# ADC.net
KiCad netlist of a schematic drawn in Altium Designer
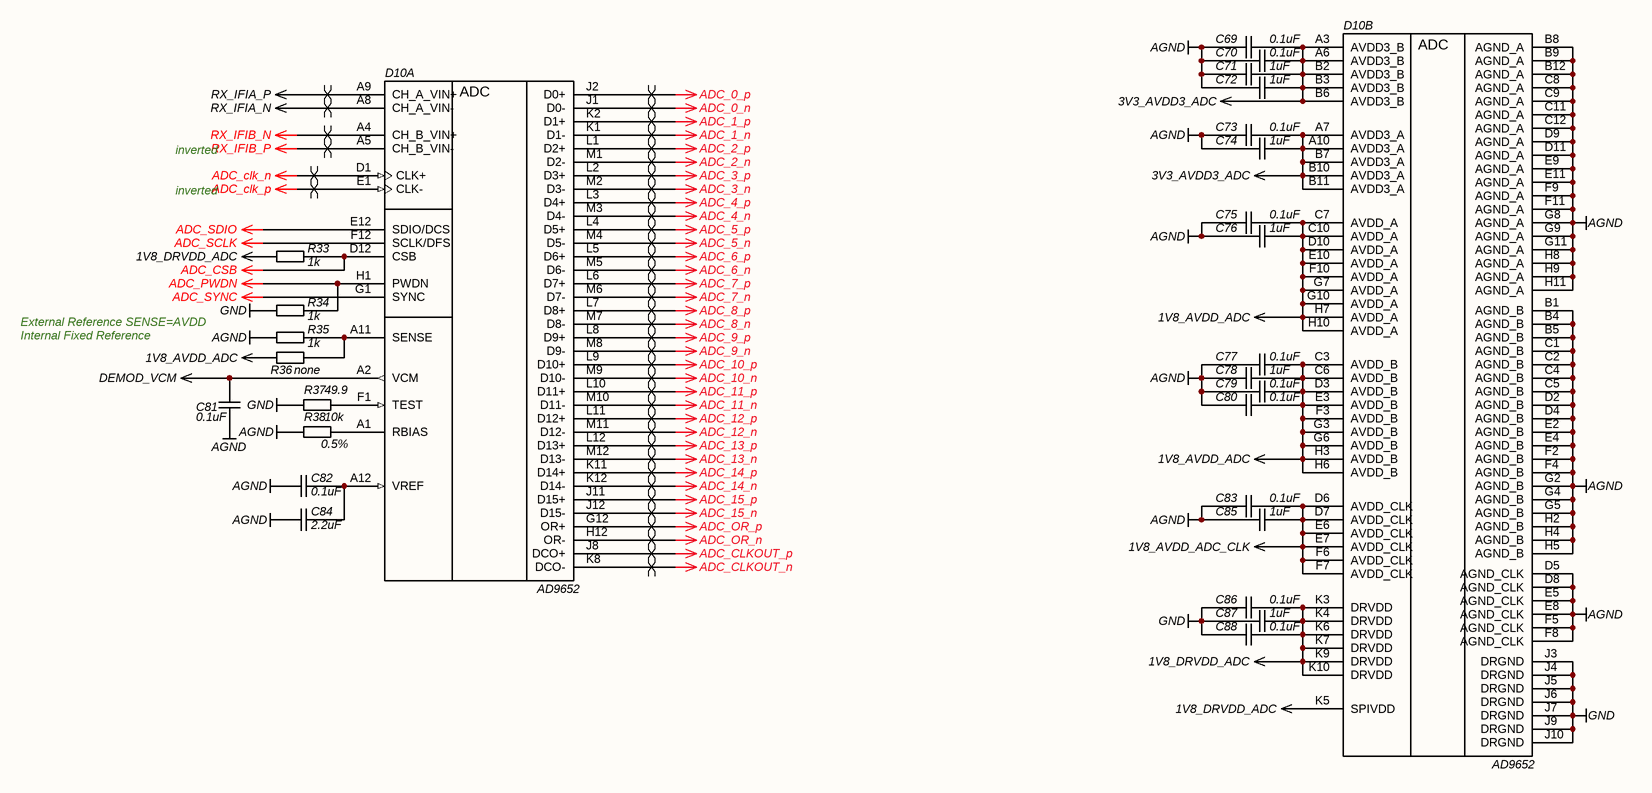
[diagram p0: ADC.SchDoc]

(export (version "E")
  (design (tool "Eeschema 10.0.6"))
  (components
    (comp (ref "C69")
      (value "0.1uF")
      (footprint "C0402")
      (description "SMD Capacitor")
      (fields (field (name "MANUFACTURER") "Murata") (field (name "TOLERANCE") "10%"))
      (libsource (lib "Kintex_SDR") (part "CAP"))
    )
    (comp (ref "C70")
      (value "0.1uF")
      (footprint "C0402")
      (description "SMD Capacitor")
      (fields (field (name "MANUFACTURER") "Murata") (field (name "TOLERANCE") "10%"))
      (libsource (lib "Kintex_SDR") (part "CAP"))
    )
    (comp (ref "C71")
      (value "1uF")
      (footprint "C0402")
      (description "SMD Capacitor")
      (fields (field (name "MANUFACTURER") "Murata") (field (name "TOLERANCE") "10%"))
      (libsource (lib "Kintex_SDR") (part "CAP"))
    )
    (comp (ref "C72")
      (value "1uF")
      (footprint "C0402")
      (description "SMD Capacitor")
      (fields (field (name "MANUFACTURER") "Murata") (field (name "TOLERANCE") "10%"))
      (libsource (lib "Kintex_SDR") (part "CAP"))
    )
    (comp (ref "C73")
      (value "0.1uF")
      (footprint "C0402")
      (description "SMD Capacitor")
      (fields (field (name "MANUFACTURER") "Murata") (field (name "TOLERANCE") "10%"))
      (libsource (lib "Kintex_SDR") (part "CAP"))
    )
    (comp (ref "C74")
      (value "1uF")
      (footprint "C0402")
      (description "SMD Capacitor")
      (fields (field (name "MANUFACTURER") "Murata") (field (name "TOLERANCE") "10%"))
      (libsource (lib "Kintex_SDR") (part "CAP"))
    )
    (comp (ref "C75")
      (value "0.1uF")
      (footprint "C0402")
      (description "SMD Capacitor")
      (fields (field (name "MANUFACTURER") "Murata") (field (name "TOLERANCE") "10%"))
      (libsource (lib "Kintex_SDR") (part "CAP"))
    )
    (comp (ref "C76")
      (value "1uF")
      (footprint "C0402")
      (description "SMD Capacitor")
      (fields (field (name "MANUFACTURER") "Murata") (field (name "TOLERANCE") "10%"))
      (libsource (lib "Kintex_SDR") (part "CAP"))
    )
    (comp (ref "C77")
      (value "0.1uF")
      (footprint "C0402")
      (description "SMD Capacitor")
      (fields (field (name "MANUFACTURER") "Murata") (field (name "TOLERANCE") "10%"))
      (libsource (lib "Kintex_SDR") (part "CAP"))
    )
    (comp (ref "C78")
      (value "1uF")
      (footprint "C0402")
      (description "SMD Capacitor")
      (fields (field (name "MANUFACTURER") "Murata") (field (name "TOLERANCE") "10%"))
      (libsource (lib "Kintex_SDR") (part "CAP"))
    )
    (comp (ref "C79")
      (value "0.1uF")
      (footprint "C0402")
      (description "SMD Capacitor")
      (fields (field (name "MANUFACTURER") "Murata") (field (name "TOLERANCE") "10%"))
      (libsource (lib "Kintex_SDR") (part "CAP"))
    )
    (comp (ref "C80")
      (value "0.1uF")
      (footprint "C0402")
      (description "SMD Capacitor")
      (fields (field (name "MANUFACTURER") "Murata") (field (name "TOLERANCE") "10%"))
      (libsource (lib "Kintex_SDR") (part "CAP"))
    )
    (comp (ref "C81")
      (value "0.1uF")
      (footprint "C0402")
      (description "SMD Capacitor")
      (fields (field (name "MANUFACTURER") "Murata") (field (name "TOLERANCE") "10%"))
      (libsource (lib "Kintex_SDR") (part "CAP"))
    )
    (comp (ref "C82")
      (value "0.1uF")
      (footprint "C0402")
      (description "SMD Capacitor")
      (fields (field (name "MANUFACTURER") "Murata") (field (name "TOLERANCE") "10%"))
      (libsource (lib "Kintex_SDR") (part "CAP"))
    )
    (comp (ref "C83")
      (value "0.1uF")
      (footprint "C0402")
      (description "SMD Capacitor")
      (fields (field (name "MANUFACTURER") "Murata") (field (name "TOLERANCE") "10%"))
      (libsource (lib "Kintex_SDR") (part "CAP"))
    )
    (comp (ref "C84")
      (value "2.2uF")
      (footprint "C0603")
      (description "SMD Capacitor")
      (fields (field (name "MANUFACTURER") "Murata") (field (name "TOLERANCE") "10%"))
      (libsource (lib "Kintex_SDR") (part "CAP"))
    )
    (comp (ref "C85")
      (value "1uF")
      (footprint "C0402")
      (description "SMD Capacitor")
      (fields (field (name "MANUFACTURER") "Murata") (field (name "TOLERANCE") "10%"))
      (libsource (lib "Kintex_SDR") (part "CAP"))
    )
    (comp (ref "C86")
      (value "0.1uF")
      (footprint "C0402")
      (description "SMD Capacitor")
      (fields (field (name "MANUFACTURER") "Murata") (field (name "TOLERANCE") "10%"))
      (libsource (lib "Kintex_SDR") (part "CAP"))
    )
    (comp (ref "C87")
      (value "1uF")
      (footprint "C0402")
      (description "SMD Capacitor")
      (fields (field (name "MANUFACTURER") "Murata") (field (name "TOLERANCE") "10%"))
      (libsource (lib "Kintex_SDR") (part "CAP"))
    )
    (comp (ref "C88")
      (value "0.1uF")
      (footprint "C0402")
      (description "SMD Capacitor")
      (fields (field (name "MANUFACTURER") "Murata") (field (name "TOLERANCE") "10%"))
      (libsource (lib "Kintex_SDR") (part "CAP"))
    )
    (comp (ref "D10")
      (value "AD9652")
      (footprint "DBLib:BGA144x12")
      (description "Dual, 16-bit analog-to-digital converter (ADC)\r\nwith sampling speeds of up to 310 MSPS")
      (fields (field (name "MANUFACTURER") "Analog Devices"))
      (libsource (lib "DBLib") (part "AD9652"))
    )
    (comp (ref "R33")
      (value "1k")
      (footprint "R0402")
      (description "SMD Resistor")
      (fields (field (name "POWER") "0.062 Wt") (field (name "TOLERANCE") "5%"))
      (libsource (lib "") (part "RES_2"))
    )
    (comp (ref "R34")
      (value "1k")
      (footprint "R0402")
      (description "SMD Resistor")
      (fields (field (name "POWER") "0.062 Wt") (field (name "TOLERANCE") "5%"))
      (libsource (lib "") (part "RES_2"))
    )
    (comp (ref "R35")
      (value "1k")
      (footprint "R0402")
      (description "SMD Resistor")
      (fields (field (name "POWER") "0.062 Wt") (field (name "TOLERANCE") "5%"))
      (libsource (lib "") (part "RES_2"))
    )
    (comp (ref "R36")
      (value "none")
      (footprint "R0402")
      (description "SMD Resistor")
      (fields
        (field (name "POWER") "0.062 Wt")
        (field (name "MANUFACTURER") "Panasonic Electronic Components")
      )
      (libsource (lib "") (part "RES_2"))
    )
    (comp (ref "R37")
      (value "49.9")
      (footprint "R0402")
      (description "SMD Resistor")
      (fields (field (name "POWER") "0.063 Wt") (field (name "TOLERANCE") "0.5%"))
      (libsource (lib "Kintex_SDR") (part "RES"))
    )
    (comp (ref "R38")
      (value "10k")
      (footprint "R0402")
      (description "SMD Resistor")
      (fields
        (field (name "POWER") "0.063 Wt")
        (field (name "TOLERANCE") "0.5%")
        (field (name "MANUFACTURER") "Panasonic Electronic Components")
      )
      (libsource (lib "") (part "RES_1"))
    )
  )
  (nets
    (net (code "1") (name "1V8_AVDD_ADC") (class "Default")
      (node (ref "C75") (pin "2") (pinfunction "2_2") (pintype "passive"))
      (node (ref "C76") (pin "2") (pinfunction "2_2") (pintype "passive"))
      (node (ref "C77") (pin "2") (pinfunction "2_2") (pintype "passive"))
      (node (ref "C78") (pin "2") (pinfunction "2_2") (pintype "passive"))
      (node (ref "C79") (pin "2") (pinfunction "2_2") (pintype "passive"))
      (node (ref "C80") (pin "2") (pinfunction "2_2") (pintype "passive"))
      (node (ref "D10") (pin "C10") (pinfunction "AVDD_A_C10") (pintype "passive"))
      (node (ref "D10") (pin "C3") (pinfunction "AVDD_B_C3") (pintype "passive"))
      (node (ref "D10") (pin "C6") (pinfunction "AVDD_B_C6") (pintype "passive"))
      (node (ref "D10") (pin "C7") (pinfunction "AVDD_A_C7") (pintype "passive"))
      (node (ref "D10") (pin "D10") (pinfunction "AVDD_A_D10") (pintype "passive"))
      (node (ref "D10") (pin "D3") (pinfunction "AVDD_B_D3") (pintype "passive"))
      (node (ref "D10") (pin "E10") (pinfunction "AVDD_A_E10") (pintype "passive"))
      (node (ref "D10") (pin "E3") (pinfunction "AVDD_B_E3") (pintype "passive"))
      (node (ref "D10") (pin "F10") (pinfunction "AVDD_A_F10") (pintype "passive"))
      (node (ref "D10") (pin "F3") (pinfunction "AVDD_B_F3") (pintype "passive"))
      (node (ref "D10") (pin "G10") (pinfunction "AVDD_A_G10") (pintype "passive"))
      (node (ref "D10") (pin "G3") (pinfunction "AVDD_B_G3") (pintype "passive"))
      (node (ref "D10") (pin "G6") (pinfunction "AVDD_B_G6") (pintype "passive"))
      (node (ref "D10") (pin "G7") (pinfunction "AVDD_A_G7") (pintype "passive"))
      (node (ref "D10") (pin "H10") (pinfunction "AVDD_A_H10") (pintype "passive"))
      (node (ref "D10") (pin "H3") (pinfunction "AVDD_B_H3") (pintype "passive"))
      (node (ref "D10") (pin "H6") (pinfunction "AVDD_B_H6") (pintype "passive"))
      (node (ref "D10") (pin "H7") (pinfunction "AVDD_A_H7") (pintype "passive"))
      (node (ref "R36") (pin "2") (pinfunction "2_2") (pintype "passive"))
    )
    (net (code "2") (name "1V8_AVDD_ADC_CLK") (class "Default")
      (node (ref "C83") (pin "2") (pinfunction "2_2") (pintype "passive"))
      (node (ref "C85") (pin "2") (pinfunction "2_2") (pintype "passive"))
      (node (ref "D10") (pin "D6") (pinfunction "AVDD_CLK_D6") (pintype "passive"))
      (node (ref "D10") (pin "D7") (pinfunction "AVDD_CLK_D7") (pintype "passive"))
      (node (ref "D10") (pin "E6") (pinfunction "AVDD_CLK_E6") (pintype "passive"))
      (node (ref "D10") (pin "E7") (pinfunction "AVDD_CLK_E7") (pintype "passive"))
      (node (ref "D10") (pin "F6") (pinfunction "AVDD_CLK_F6") (pintype "passive"))
      (node (ref "D10") (pin "F7") (pinfunction "AVDD_CLK_F7") (pintype "passive"))
    )
    (net (code "3") (name "1V8_DRVDD_ADC") (class "Default")
      (node (ref "C86") (pin "2") (pinfunction "2_2") (pintype "passive"))
      (node (ref "C87") (pin "2") (pinfunction "2_2") (pintype "passive"))
      (node (ref "C88") (pin "2") (pinfunction "2_2") (pintype "passive"))
      (node (ref "D10") (pin "K10") (pinfunction "DRVDD_K10") (pintype "passive"))
      (node (ref "D10") (pin "K3") (pinfunction "DRVDD_K3") (pintype "passive"))
      (node (ref "D10") (pin "K4") (pinfunction "DRVDD_K4") (pintype "passive"))
      (node (ref "D10") (pin "K5") (pinfunction "SPIVDD_K5") (pintype "passive"))
      (node (ref "D10") (pin "K6") (pinfunction "DRVDD_K6") (pintype "passive"))
      (node (ref "D10") (pin "K7") (pinfunction "DRVDD_K7") (pintype "passive"))
      (node (ref "D10") (pin "K9") (pinfunction "DRVDD_K9") (pintype "passive"))
      (node (ref "R33") (pin "2") (pinfunction "2_2") (pintype "passive"))
    )
    (net (code "4") (name "3V3_AVDD3_ADC") (class "Default")
      (node (ref "C69") (pin "2") (pinfunction "2_2") (pintype "passive"))
      (node (ref "C70") (pin "2") (pinfunction "2_2") (pintype "passive"))
      (node (ref "C71") (pin "2") (pinfunction "2_2") (pintype "passive"))
      (node (ref "C72") (pin "2") (pinfunction "2_2") (pintype "passive"))
      (node (ref "C73") (pin "2") (pinfunction "2_2") (pintype "passive"))
      (node (ref "C74") (pin "2") (pinfunction "2_2") (pintype "passive"))
      (node (ref "D10") (pin "A10") (pinfunction "AVDD3_A_A10") (pintype "passive"))
      (node (ref "D10") (pin "A3") (pinfunction "AVDD3_B_A3") (pintype "passive"))
      (node (ref "D10") (pin "A6") (pinfunction "AVDD3_B_A6") (pintype "passive"))
      (node (ref "D10") (pin "A7") (pinfunction "AVDD3_A_A7") (pintype "passive"))
      (node (ref "D10") (pin "B10") (pinfunction "AVDD3_A_B10") (pintype "passive"))
      (node (ref "D10") (pin "B11") (pinfunction "AVDD3_A_B11") (pintype "passive"))
      (node (ref "D10") (pin "B2") (pinfunction "AVDD3_B_B2") (pintype "passive"))
      (node (ref "D10") (pin "B3") (pinfunction "AVDD3_B_B3") (pintype "passive"))
      (node (ref "D10") (pin "B6") (pinfunction "AVDD3_B_B6") (pintype "passive"))
      (node (ref "D10") (pin "B7") (pinfunction "AVDD3_A_B7") (pintype "passive"))
    )
    (net (code "5") (name "ADC_0_n") (class "Default")
      (node (ref "D10") (pin "J1") (pinfunction "D0-_J1") (pintype "passive"))
    )
    (net (code "6") (name "ADC_0_p") (class "Default")
      (node (ref "D10") (pin "J2") (pinfunction "D0+_J2") (pintype "passive"))
    )
    (net (code "7") (name "ADC_1_n") (class "Default")
      (node (ref "D10") (pin "K1") (pinfunction "D1-_K1") (pintype "passive"))
    )
    (net (code "8") (name "ADC_1_p") (class "Default")
      (node (ref "D10") (pin "K2") (pinfunction "D1+_K2") (pintype "passive"))
    )
    (net (code "9") (name "ADC_2_n") (class "Default")
      (node (ref "D10") (pin "M1") (pinfunction "D2-_M1") (pintype "passive"))
    )
    (net (code "10") (name "ADC_2_p") (class "Default")
      (node (ref "D10") (pin "L1") (pinfunction "D2+_L1") (pintype "passive"))
    )
    (net (code "11") (name "ADC_3_n") (class "Default")
      (node (ref "D10") (pin "M2") (pinfunction "D3-_M2") (pintype "passive"))
    )
    (net (code "12") (name "ADC_3_p") (class "Default")
      (node (ref "D10") (pin "L2") (pinfunction "D3+_L2") (pintype "passive"))
    )
    (net (code "13") (name "ADC_4_n") (class "Default")
      (node (ref "D10") (pin "M3") (pinfunction "D4-_M3") (pintype "passive"))
    )
    (net (code "14") (name "ADC_4_p") (class "Default")
      (node (ref "D10") (pin "L3") (pinfunction "D4+_L3") (pintype "passive"))
    )
    (net (code "15") (name "ADC_5_n") (class "Default")
      (node (ref "D10") (pin "M4") (pinfunction "D5-_M4") (pintype "passive"))
    )
    (net (code "16") (name "ADC_5_p") (class "Default")
      (node (ref "D10") (pin "L4") (pinfunction "D5+_L4") (pintype "passive"))
    )
    (net (code "17") (name "ADC_6_n") (class "Default")
      (node (ref "D10") (pin "M5") (pinfunction "D6-_M5") (pintype "passive"))
    )
    (net (code "18") (name "ADC_6_p") (class "Default")
      (node (ref "D10") (pin "L5") (pinfunction "D6+_L5") (pintype "passive"))
    )
    (net (code "19") (name "ADC_7_n") (class "Default")
      (node (ref "D10") (pin "M6") (pinfunction "D7-_M6") (pintype "passive"))
    )
    (net (code "20") (name "ADC_7_p") (class "Default")
      (node (ref "D10") (pin "L6") (pinfunction "D7+_L6") (pintype "passive"))
    )
    (net (code "21") (name "ADC_8_n") (class "Default")
      (node (ref "D10") (pin "M7") (pinfunction "D8-_M7") (pintype "passive"))
    )
    (net (code "22") (name "ADC_8_p") (class "Default")
      (node (ref "D10") (pin "L7") (pinfunction "D8+_L7") (pintype "passive"))
    )
    (net (code "23") (name "ADC_9_n") (class "Default")
      (node (ref "D10") (pin "M8") (pinfunction "D9-_M8") (pintype "passive"))
    )
    (net (code "24") (name "ADC_9_p") (class "Default")
      (node (ref "D10") (pin "L8") (pinfunction "D9+_L8") (pintype "passive"))
    )
    (net (code "25") (name "ADC_10_n") (class "Default")
      (node (ref "D10") (pin "M9") (pinfunction "D10-_M9") (pintype "passive"))
    )
    (net (code "26") (name "ADC_10_p") (class "Default")
      (node (ref "D10") (pin "L9") (pinfunction "D10+_L9") (pintype "passive"))
    )
    (net (code "27") (name "ADC_11_n") (class "Default")
      (node (ref "D10") (pin "M10") (pinfunction "D11-_M10") (pintype "passive"))
    )
    (net (code "28") (name "ADC_11_p") (class "Default")
      (node (ref "D10") (pin "L10") (pinfunction "D11+_L10") (pintype "passive"))
    )
    (net (code "29") (name "ADC_12_n") (class "Default")
      (node (ref "D10") (pin "M11") (pinfunction "D12-_M11") (pintype "passive"))
    )
    (net (code "30") (name "ADC_12_p") (class "Default")
      (node (ref "D10") (pin "L11") (pinfunction "D12+_L11") (pintype "passive"))
    )
    (net (code "31") (name "ADC_13_n") (class "Default")
      (node (ref "D10") (pin "M12") (pinfunction "D13-_M12") (pintype "passive"))
    )
    (net (code "32") (name "ADC_13_p") (class "Default")
      (node (ref "D10") (pin "L12") (pinfunction "D13+_L12") (pintype "passive"))
    )
    (net (code "33") (name "ADC_14_n") (class "Default")
      (node (ref "D10") (pin "K12") (pinfunction "D14-_K12") (pintype "passive"))
    )
    (net (code "34") (name "ADC_14_p") (class "Default")
      (node (ref "D10") (pin "K11") (pinfunction "D14+_K11") (pintype "passive"))
    )
    (net (code "35") (name "ADC_15_n") (class "Default")
      (node (ref "D10") (pin "J12") (pinfunction "D15-_J12") (pintype "passive"))
    )
    (net (code "36") (name "ADC_15_p") (class "Default")
      (node (ref "D10") (pin "J11") (pinfunction "D15+_J11") (pintype "passive"))
    )
    (net (code "37") (name "ADC_CLKOUT_n") (class "Default")
      (node (ref "D10") (pin "K8") (pinfunction "DCO-_K8") (pintype "passive"))
    )
    (net (code "38") (name "ADC_CLKOUT_p") (class "Default")
      (node (ref "D10") (pin "J8") (pinfunction "DCO+_J8") (pintype "passive"))
    )
    (net (code "39") (name "ADC_CSB") (class "Default")
      (node (ref "D10") (pin "D12") (pinfunction "CSB_D12") (pintype "passive"))
      (node (ref "R33") (pin "1") (pinfunction "1_1") (pintype "passive"))
    )
    (net (code "40") (name "ADC_OR_n") (class "Default")
      (node (ref "D10") (pin "H12") (pinfunction "OR-_H12") (pintype "passive"))
    )
    (net (code "41") (name "ADC_OR_p") (class "Default")
      (node (ref "D10") (pin "G12") (pinfunction "OR+_G12") (pintype "passive"))
    )
    (net (code "42") (name "ADC_PWDN") (class "Default")
      (node (ref "D10") (pin "H1") (pinfunction "PWDN_H1") (pintype "passive"))
      (node (ref "R34") (pin "1") (pinfunction "1_1") (pintype "passive"))
    )
    (net (code "43") (name "ADC_SCLK") (class "Default")
      (node (ref "D10") (pin "F12") (pinfunction "SCLK/DFS_F12") (pintype "passive"))
    )
    (net (code "44") (name "ADC_SDIO") (class "Default")
      (node (ref "D10") (pin "E12") (pinfunction "SDIO/DCS_E12") (pintype "passive"))
    )
    (net (code "45") (name "ADC_SYNC") (class "Default")
      (node (ref "D10") (pin "G1") (pinfunction "SYNC_G1") (pintype "passive"))
    )
    (net (code "46") (name "ADC_clk_n") (class "Default")
      (node (ref "D10") (pin "D1") (pinfunction "CLK+_D1") (pintype "input"))
    )
    (net (code "47") (name "ADC_clk_p") (class "Default")
      (node (ref "D10") (pin "E1") (pinfunction "CLK-_E1") (pintype "input"))
    )
    (net (code "48") (name "AGND") (class "Default")
      (node (ref "C69") (pin "1") (pinfunction "1_1") (pintype "passive"))
      (node (ref "C70") (pin "1") (pinfunction "1_1") (pintype "passive"))
      (node (ref "C71") (pin "1") (pinfunction "1_1") (pintype "passive"))
      (node (ref "C72") (pin "1") (pinfunction "1_1") (pintype "passive"))
      (node (ref "C73") (pin "1") (pinfunction "1_1") (pintype "passive"))
      (node (ref "C74") (pin "1") (pinfunction "1_1") (pintype "passive"))
      (node (ref "C75") (pin "1") (pinfunction "1_1") (pintype "passive"))
      (node (ref "C76") (pin "1") (pinfunction "1_1") (pintype "passive"))
      (node (ref "C77") (pin "1") (pinfunction "1_1") (pintype "passive"))
      (node (ref "C78") (pin "1") (pinfunction "1_1") (pintype "passive"))
      (node (ref "C79") (pin "1") (pinfunction "1_1") (pintype "passive"))
      (node (ref "C80") (pin "1") (pinfunction "1_1") (pintype "passive"))
      (node (ref "C81") (pin "1") (pinfunction "1_1") (pintype "passive"))
      (node (ref "C82") (pin "1") (pinfunction "1_1") (pintype "passive"))
      (node (ref "C83") (pin "1") (pinfunction "1_1") (pintype "passive"))
      (node (ref "C84") (pin "2") (pinfunction "2_2") (pintype "passive"))
      (node (ref "C85") (pin "1") (pinfunction "1_1") (pintype "passive"))
      (node (ref "D10") (pin "B1") (pinfunction "AGND_B_B1") (pintype "passive"))
      (node (ref "D10") (pin "B12") (pinfunction "AGND_A_B12") (pintype "passive"))
      (node (ref "D10") (pin "B4") (pinfunction "AGND_B_B4") (pintype "passive"))
      (node (ref "D10") (pin "B5") (pinfunction "AGND_B_B5") (pintype "passive"))
      (node (ref "D10") (pin "B8") (pinfunction "AGND_A_B8") (pintype "passive"))
      (node (ref "D10") (pin "B9") (pinfunction "AGND_A_B9") (pintype "passive"))
      (node (ref "D10") (pin "C1") (pinfunction "AGND_B_C1") (pintype "passive"))
      (node (ref "D10") (pin "C11") (pinfunction "AGND_A_C11") (pintype "passive"))
      (node (ref "D10") (pin "C12") (pinfunction "AGND_A_C12") (pintype "passive"))
      (node (ref "D10") (pin "C2") (pinfunction "AGND_B_C2") (pintype "passive"))
      (node (ref "D10") (pin "C4") (pinfunction "AGND_B_C4") (pintype "passive"))
      (node (ref "D10") (pin "C5") (pinfunction "AGND_B_C5") (pintype "passive"))
      (node (ref "D10") (pin "C8") (pinfunction "AGND_A_C8") (pintype "passive"))
      (node (ref "D10") (pin "C9") (pinfunction "AGND_A_C9") (pintype "passive"))
      (node (ref "D10") (pin "D11") (pinfunction "AGND_A_D11") (pintype "passive"))
      (node (ref "D10") (pin "D2") (pinfunction "AGND_B_D2") (pintype "passive"))
      (node (ref "D10") (pin "D4") (pinfunction "AGND_B_D4") (pintype "passive"))
      (node (ref "D10") (pin "D5") (pinfunction "AGND_CLK_D5") (pintype "passive"))
      (node (ref "D10") (pin "D8") (pinfunction "AGND_CLK_D8") (pintype "passive"))
      (node (ref "D10") (pin "D9") (pinfunction "AGND_A_D9") (pintype "passive"))
      (node (ref "D10") (pin "E11") (pinfunction "AGND_A_E11") (pintype "passive"))
      (node (ref "D10") (pin "E2") (pinfunction "AGND_B_E2") (pintype "passive"))
      (node (ref "D10") (pin "E4") (pinfunction "AGND_B_E4") (pintype "passive"))
      (node (ref "D10") (pin "E5") (pinfunction "AGND_CLK_E5") (pintype "passive"))
      (node (ref "D10") (pin "E8") (pinfunction "AGND_CLK_E8") (pintype "passive"))
      (node (ref "D10") (pin "E9") (pinfunction "AGND_A_E9") (pintype "passive"))
      (node (ref "D10") (pin "F11") (pinfunction "AGND_A_F11") (pintype "passive"))
      (node (ref "D10") (pin "F2") (pinfunction "AGND_B_F2") (pintype "passive"))
      (node (ref "D10") (pin "F4") (pinfunction "AGND_B_F4") (pintype "passive"))
      (node (ref "D10") (pin "F5") (pinfunction "AGND_CLK_F5") (pintype "passive"))
      (node (ref "D10") (pin "F8") (pinfunction "AGND_CLK_F8") (pintype "passive"))
      (node (ref "D10") (pin "F9") (pinfunction "AGND_A_F9") (pintype "passive"))
      (node (ref "D10") (pin "G11") (pinfunction "AGND_A_G11") (pintype "passive"))
      (node (ref "D10") (pin "G2") (pinfunction "AGND_B_G2") (pintype "passive"))
      (node (ref "D10") (pin "G4") (pinfunction "AGND_B_G4") (pintype "passive"))
      (node (ref "D10") (pin "G5") (pinfunction "AGND_B_G5") (pintype "passive"))
      (node (ref "D10") (pin "G8") (pinfunction "AGND_A_G8") (pintype "passive"))
      (node (ref "D10") (pin "G9") (pinfunction "AGND_A_G9") (pintype "passive"))
      (node (ref "D10") (pin "H11") (pinfunction "AGND_A_H11") (pintype "passive"))
      (node (ref "D10") (pin "H2") (pinfunction "AGND_B_H2") (pintype "passive"))
      (node (ref "D10") (pin "H4") (pinfunction "AGND_B_H4") (pintype "passive"))
      (node (ref "D10") (pin "H5") (pinfunction "AGND_B_H5") (pintype "passive"))
      (node (ref "D10") (pin "H8") (pinfunction "AGND_A_H8") (pintype "passive"))
      (node (ref "D10") (pin "H9") (pinfunction "AGND_A_H9") (pintype "passive"))
      (node (ref "R35") (pin "2") (pinfunction "2_2") (pintype "passive"))
      (node (ref "R38") (pin "2") (pinfunction "2_2") (pintype "passive"))
    )
    (net (code "49") (name "DEMOD_VCM") (class "Default")
      (node (ref "C81") (pin "2") (pinfunction "2_2") (pintype "passive"))
      (node (ref "D10") (pin "A2") (pinfunction "VCM_A2") (pintype "output"))
    )
    (net (code "50") (name "GND") (class "Default")
      (node (ref "C86") (pin "1") (pinfunction "1_1") (pintype "passive"))
      (node (ref "C87") (pin "1") (pinfunction "1_1") (pintype "passive"))
      (node (ref "C88") (pin "1") (pinfunction "1_1") (pintype "passive"))
      (node (ref "D10") (pin "J10") (pinfunction "DRGND_J10") (pintype "passive"))
      (node (ref "D10") (pin "J3") (pinfunction "DRGND_J3") (pintype "passive"))
      (node (ref "D10") (pin "J4") (pinfunction "DRGND_J4") (pintype "passive"))
      (node (ref "D10") (pin "J5") (pinfunction "DRGND_J5") (pintype "passive"))
      (node (ref "D10") (pin "J6") (pinfunction "DRGND_J6") (pintype "passive"))
      (node (ref "D10") (pin "J7") (pinfunction "DRGND_J7") (pintype "passive"))
      (node (ref "D10") (pin "J9") (pinfunction "DRGND_J9") (pintype "passive"))
      (node (ref "R34") (pin "2") (pinfunction "2_2") (pintype "passive"))
      (node (ref "R37") (pin "1") (pinfunction "1_1") (pintype "passive"))
    )
    (net (code "51") (name "Net-(D10A-RBIAS)") (class "Default")
      (node (ref "D10") (pin "A1") (pinfunction "RBIAS_A1") (pintype "passive"))
      (node (ref "R38") (pin "1") (pinfunction "1_1") (pintype "passive"))
    )
    (net (code "52") (name "Net-(D10A-SENSE)") (class "Default")
      (node (ref "D10") (pin "A11") (pinfunction "SENSE_A11") (pintype "passive"))
      (node (ref "R35") (pin "1") (pinfunction "1_1") (pintype "passive"))
      (node (ref "R36") (pin "1") (pinfunction "1_1") (pintype "passive"))
    )
    (net (code "53") (name "Net-(D10A-TEST)") (class "Default")
      (node (ref "D10") (pin "F1") (pinfunction "TEST_F1") (pintype "input"))
      (node (ref "R37") (pin "2") (pinfunction "2_2") (pintype "passive"))
    )
    (net (code "54") (name "Net-(D10A-VREF)") (class "Default")
      (node (ref "C82") (pin "2") (pinfunction "2_2") (pintype "passive"))
      (node (ref "C84") (pin "1") (pinfunction "1_1") (pintype "passive"))
      (node (ref "D10") (pin "A12") (pinfunction "VREF_A12") (pintype "input"))
    )
    (net (code "55") (name "RX_IFIA_N") (class "Default")
      (node (ref "D10") (pin "A8") (pinfunction "CH_A_VIN-_A8") (pintype "passive"))
    )
    (net (code "56") (name "RX_IFIA_P") (class "Default")
      (node (ref "D10") (pin "A9") (pinfunction "CH_A_VIN+_A9") (pintype "passive"))
    )
    (net (code "57") (name "RX_IFIB_N") (class "Default")
      (node (ref "D10") (pin "A4") (pinfunction "CH_B_VIN+_A4") (pintype "passive"))
    )
    (net (code "58") (name "RX_IFIB_P") (class "Default")
      (node (ref "D10") (pin "A5") (pinfunction "CH_B_VIN-_A5") (pintype "passive"))
    )
  )
)
